# USB_Charger.net
KiCad netlist of a schematic drawn in Altium Designer
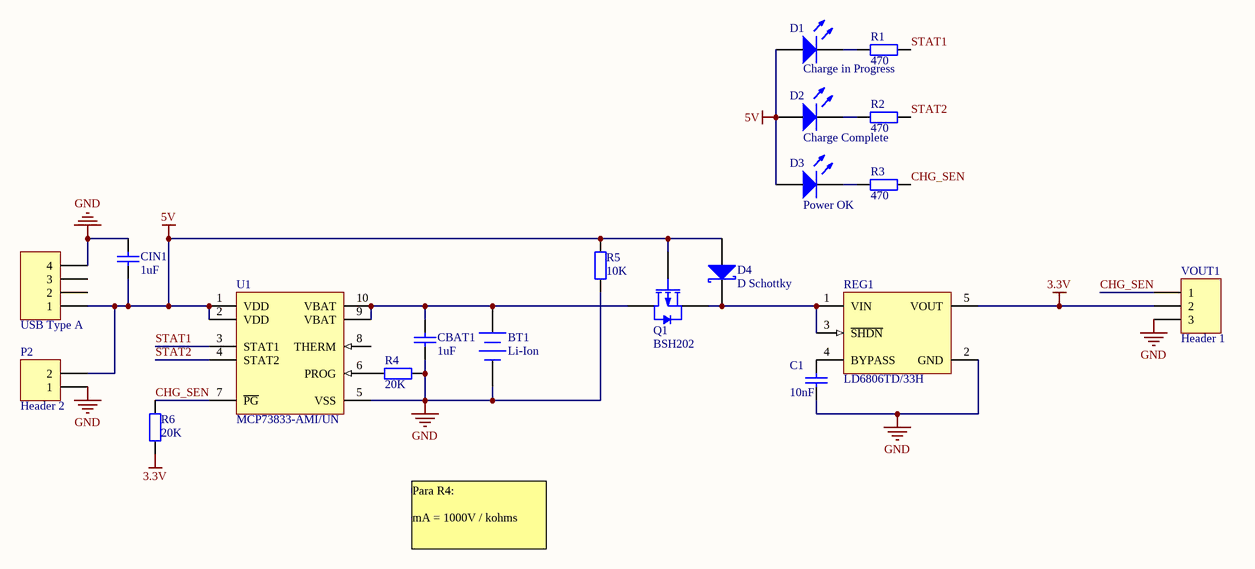
[diagram p0: USB_Charger.SchDoc]

(export (version "E")
  (design (tool "Eeschema 10.0.6"))
  (components
    (comp (ref "BT1")
      (value "Li-Ion")
      (footprint "BAT-2")
      (description "Multicell Battery")
      (fields (field (name "PUBLISHER") "Altium Limited"))
      (libsource (lib "Miscellaneous Devices") (part "Battery"))
    )
    (comp (ref "C1")
      (value "10nF")
      (footprint "1608[0603]")
      (description "Capacitor")
      (fields (field (name "Comment") "Cap") (field (name "PUBLISHER") "Altium Limited"))
      (libsource (lib "Miscellaneous Devices") (part "Cap"))
    )
    (comp (ref "CBAT1")
      (value "1uF")
      (footprint "1608[0603]")
      (description "Capacitor")
      (fields (field (name "Comment") "Cap") (field (name "PUBLISHER") "Altium Limited"))
      (libsource (lib "Miscellaneous Devices") (part "Cap"))
    )
    (comp (ref "CIN1")
      (value "1uF")
      (footprint "1608[0603]")
      (description "Capacitor")
      (fields (field (name "Comment") "Cap") (field (name "PUBLISHER") "Altium Limited"))
      (libsource (lib "Miscellaneous Devices") (part "Cap"))
    )
    (comp (ref "D1")
      (value "Charge in Progress")
      (footprint "2013[0805]")
      (libsource (lib "LibreriaComponentes") (part "LED SMD (0603)"))
    )
    (comp (ref "D2")
      (value "Charge Complete")
      (footprint "2013[0805]")
      (libsource (lib "LibreriaComponentes") (part "LED SMD (0603)"))
    )
    (comp (ref "D3")
      (value "Power OK")
      (footprint "2013[0805]")
      (libsource (lib "LibreriaComponentes") (part "LED SMD (0603)"))
    )
    (comp (ref "D4")
      (value "D Schottky")
      (footprint "SOD123/X.85")
      (description "Schottky Diode")
      (fields (field (name "PUBLISHER") "Altium Limited"))
      (libsource (lib "Miscellaneous Devices") (part "D Schottky"))
    )
    (comp (ref "P1")
      (value "USB Type A")
      (footprint "USBA_SMD")
      (description "Header, 4-Pin")
      (fields (field (name "PUBLISHER") "Altium Limited"))
      (libsource (lib "Miscellaneous Connectors") (part "Header 4"))
    )
    (comp (ref "P2")
      (value "Header 2")
      (footprint "HDR1X2")
      (description "Header, 2-Pin")
      (fields (field (name "PUBLISHER") "Altium Limited"))
      (libsource (lib "Miscellaneous Connectors") (part "Header 2"))
    )
    (comp (ref "Q1")
      (value "BSH202")
      (footprint "SOT23_M")
      (description "P-channel Enhancement Mode MOSFET")
      (fields (field (name "PUBLISHER") "Altium Limited"))
      (libsource (lib "Philips Discrete MOSFET - Low Power") (part "BSH202"))
    )
    (comp (ref "R1")
      (value "470")
      (footprint "1608[0603]")
      (description "Resistor")
      (fields (field (name "Comment") "Res2") (field (name "PUBLISHER") "Altium Limited"))
      (libsource (lib "") (part "Res2_1"))
    )
    (comp (ref "R2")
      (value "470")
      (footprint "1608[0603]")
      (description "Resistor")
      (fields (field (name "Comment") "Res2") (field (name "PUBLISHER") "Altium Limited"))
      (libsource (lib "") (part "Res2_1"))
    )
    (comp (ref "R3")
      (value "470")
      (footprint "1608[0603]")
      (description "Resistor")
      (fields (field (name "Comment") "Res2") (field (name "PUBLISHER") "Altium Limited"))
      (libsource (lib "") (part "Res2_1"))
    )
    (comp (ref "R4")
      (value "20K")
      (footprint "1608[0603]")
      (description "Resistor")
      (fields (field (name "Comment") "Res2") (field (name "PUBLISHER") "Altium Limited"))
      (libsource (lib "Miscellaneous Devices") (part "Res2"))
    )
    (comp (ref "R5")
      (value "10K")
      (footprint "1608[0603]")
      (description "Resistor")
      (fields (field (name "Comment") "Res2") (field (name "PUBLISHER") "Altium Limited"))
      (libsource (lib "") (part "Res2_2"))
    )
    (comp (ref "R6")
      (value "20K")
      (footprint "1608[0603]")
      (description "Resistor")
      (fields (field (name "Comment") "Res2") (field (name "PUBLISHER") "Altium Limited"))
      (libsource (lib "") (part "Res2_2"))
    )
    (comp (ref "REG1")
      (value "LD6806TD/33H")
      (footprint "DBV005_N")
      (fields (field (name "PUBLISHER") "Altium Limited"))
      (libsource (lib "Microchip Power Mgt Line Regulator") (part "TC1014-1.8VCT713"))
    )
    (comp (ref "U1")
      (value "MCP73833-AMI/UN")
      (footprint "MSOP-UN10_N")
      (fields (field (name "PUBLISHER") "Altium Limited"))
      (libsource (lib "Microchip Power Mgt Battery Management") (part "MCP73833-AMI/UN"))
    )
    (comp (ref "VOUT1")
      (value "Header 1")
      (footprint "HDR1X3H")
      (description "Header, 3-Pin")
      (fields (field (name "PUBLISHER") "Altium Limited"))
      (libsource (lib "Miscellaneous Connectors") (part "Header 3"))
    )
  )
  (nets
    (net (code "1") (name "/CHG_SEN") (class "Default")
      (node (ref "R3") (pin "2") (pinfunction "2_2") (pintype "passive"))
      (node (ref "R6") (pin "1") (pinfunction "1_1") (pintype "passive"))
      (node (ref "U1") (pin "7") (pinfunction "~{PG}_7") (pintype "open_collector"))
      (node (ref "VOUT1") (pin "1") (pinfunction "1_1") (pintype "passive"))
    )
    (net (code "2") (name "/STAT1") (class "Default")
      (node (ref "R1") (pin "2") (pinfunction "2_2") (pintype "passive"))
      (node (ref "U1") (pin "3") (pinfunction "STAT1_3") (pintype "open_collector"))
    )
    (net (code "3") (name "/STAT2") (class "Default")
      (node (ref "R2") (pin "2") (pinfunction "2_2") (pintype "passive"))
      (node (ref "U1") (pin "4") (pinfunction "STAT2_4") (pintype "open_collector"))
    )
    (net (code "4") (name "3.3V") (class "Default")
      (node (ref "R6") (pin "2") (pinfunction "2_2") (pintype "passive"))
      (node (ref "REG1") (pin "5") (pinfunction "VOUT_5") (pintype "power_in"))
      (node (ref "VOUT1") (pin "2") (pinfunction "2_2") (pintype "passive"))
    )
    (net (code "5") (name "5V") (class "Default")
      (node (ref "CIN1") (pin "2") (pinfunction "2_2") (pintype "passive"))
      (node (ref "D1") (pin "1") (pinfunction "1_1") (pintype "passive"))
      (node (ref "D2") (pin "1") (pinfunction "1_1") (pintype "passive"))
      (node (ref "D3") (pin "1") (pinfunction "1_1") (pintype "passive"))
      (node (ref "D4") (pin "1") (pinfunction "A_1") (pintype "passive"))
      (node (ref "P1") (pin "1") (pinfunction "1_1") (pintype "passive"))
      (node (ref "P2") (pin "2") (pinfunction "2_2") (pintype "passive"))
      (node (ref "Q1") (pin "1") (pinfunction "G_1") (pintype "passive"))
      (node (ref "R5") (pin "1") (pinfunction "1_1") (pintype "passive"))
      (node (ref "U1") (pin "1") (pinfunction "VDD_1") (pintype "power_in"))
      (node (ref "U1") (pin "2") (pinfunction "VDD_2") (pintype "power_in"))
    )
    (net (code "6") (name "GND") (class "Default")
      (node (ref "BT1") (pin "2") (pinfunction "-_2") (pintype "passive"))
      (node (ref "C1") (pin "1") (pinfunction "1_1") (pintype "passive"))
      (node (ref "CBAT1") (pin "2") (pinfunction "2_2") (pintype "passive"))
      (node (ref "CIN1") (pin "1") (pinfunction "1_1") (pintype "passive"))
      (node (ref "P1") (pin "4") (pinfunction "4_4") (pintype "passive"))
      (node (ref "P2") (pin "1") (pinfunction "1_1") (pintype "passive"))
      (node (ref "R4") (pin "1") (pinfunction "1_1") (pintype "passive"))
      (node (ref "R5") (pin "2") (pinfunction "2_2") (pintype "passive"))
      (node (ref "REG1") (pin "2") (pinfunction "GND_2") (pintype "power_in"))
      (node (ref "U1") (pin "5") (pinfunction "VSS_5") (pintype "power_in"))
      (node (ref "VOUT1") (pin "3") (pinfunction "3_3") (pintype "passive"))
    )
    (net (code "7") (name "Net-(BT1-+)") (class "Default")
      (node (ref "BT1") (pin "1") (pinfunction "+_1") (pintype "passive"))
      (node (ref "CBAT1") (pin "1") (pinfunction "1_1") (pintype "passive"))
      (node (ref "Q1") (pin "3") (pinfunction "D_3") (pintype "passive"))
      (node (ref "U1") (pin "10") (pinfunction "VBAT_10") (pintype "power_in"))
      (node (ref "U1") (pin "9") (pinfunction "VBAT_9") (pintype "power_in"))
    )
    (net (code "8") (name "Net-(D1-Pad2)") (class "Default")
      (node (ref "D1") (pin "2") (pinfunction "2_2") (pintype "passive"))
      (node (ref "R1") (pin "1") (pinfunction "1_1") (pintype "passive"))
    )
    (net (code "9") (name "Net-(D2-Pad2)") (class "Default")
      (node (ref "D2") (pin "2") (pinfunction "2_2") (pintype "passive"))
      (node (ref "R2") (pin "1") (pinfunction "1_1") (pintype "passive"))
    )
    (net (code "10") (name "Net-(D3-Pad2)") (class "Default")
      (node (ref "D3") (pin "2") (pinfunction "2_2") (pintype "passive"))
      (node (ref "R3") (pin "1") (pinfunction "1_1") (pintype "passive"))
    )
    (net (code "11") (name "Net-(D4-K)") (class "Default")
      (node (ref "D4") (pin "2") (pinfunction "K_2") (pintype "passive"))
      (node (ref "Q1") (pin "2") (pinfunction "S_2") (pintype "passive"))
      (node (ref "REG1") (pin "1") (pinfunction "VIN_1") (pintype "power_in"))
      (node (ref "REG1") (pin "3") (pinfunction "~{SHDN}_3") (pintype "input"))
    )
    (net (code "12") (name "Net-(REG1-BYPASS)") (class "Default")
      (node (ref "C1") (pin "2") (pinfunction "2_2") (pintype "passive"))
      (node (ref "REG1") (pin "4") (pinfunction "BYPASS_4") (pintype "passive"))
    )
    (net (code "13") (name "Net-(U1-PROG)") (class "Default")
      (node (ref "R4") (pin "2") (pinfunction "2_2") (pintype "passive"))
      (node (ref "U1") (pin "6") (pinfunction "PROG_6") (pintype "input"))
    )
    (net (code "14") (name "unconnected-(P1-Pad2)") (class "Default")
      (node (ref "P1") (pin "2") (pinfunction "2_2") (pintype "passive"))
    )
    (net (code "15") (name "unconnected-(P1-Pad3)") (class "Default")
      (node (ref "P1") (pin "3") (pinfunction "3_3") (pintype "passive"))
    )
    (net (code "16") (name "unconnected-(U1-THERM-Pad8)") (class "Default")
      (node (ref "U1") (pin "8") (pinfunction "THERM_8") (pintype "input"))
    )
  )
)
